# rng_1_0.net
KiCad netlist of a schematic drawn in EAGLE
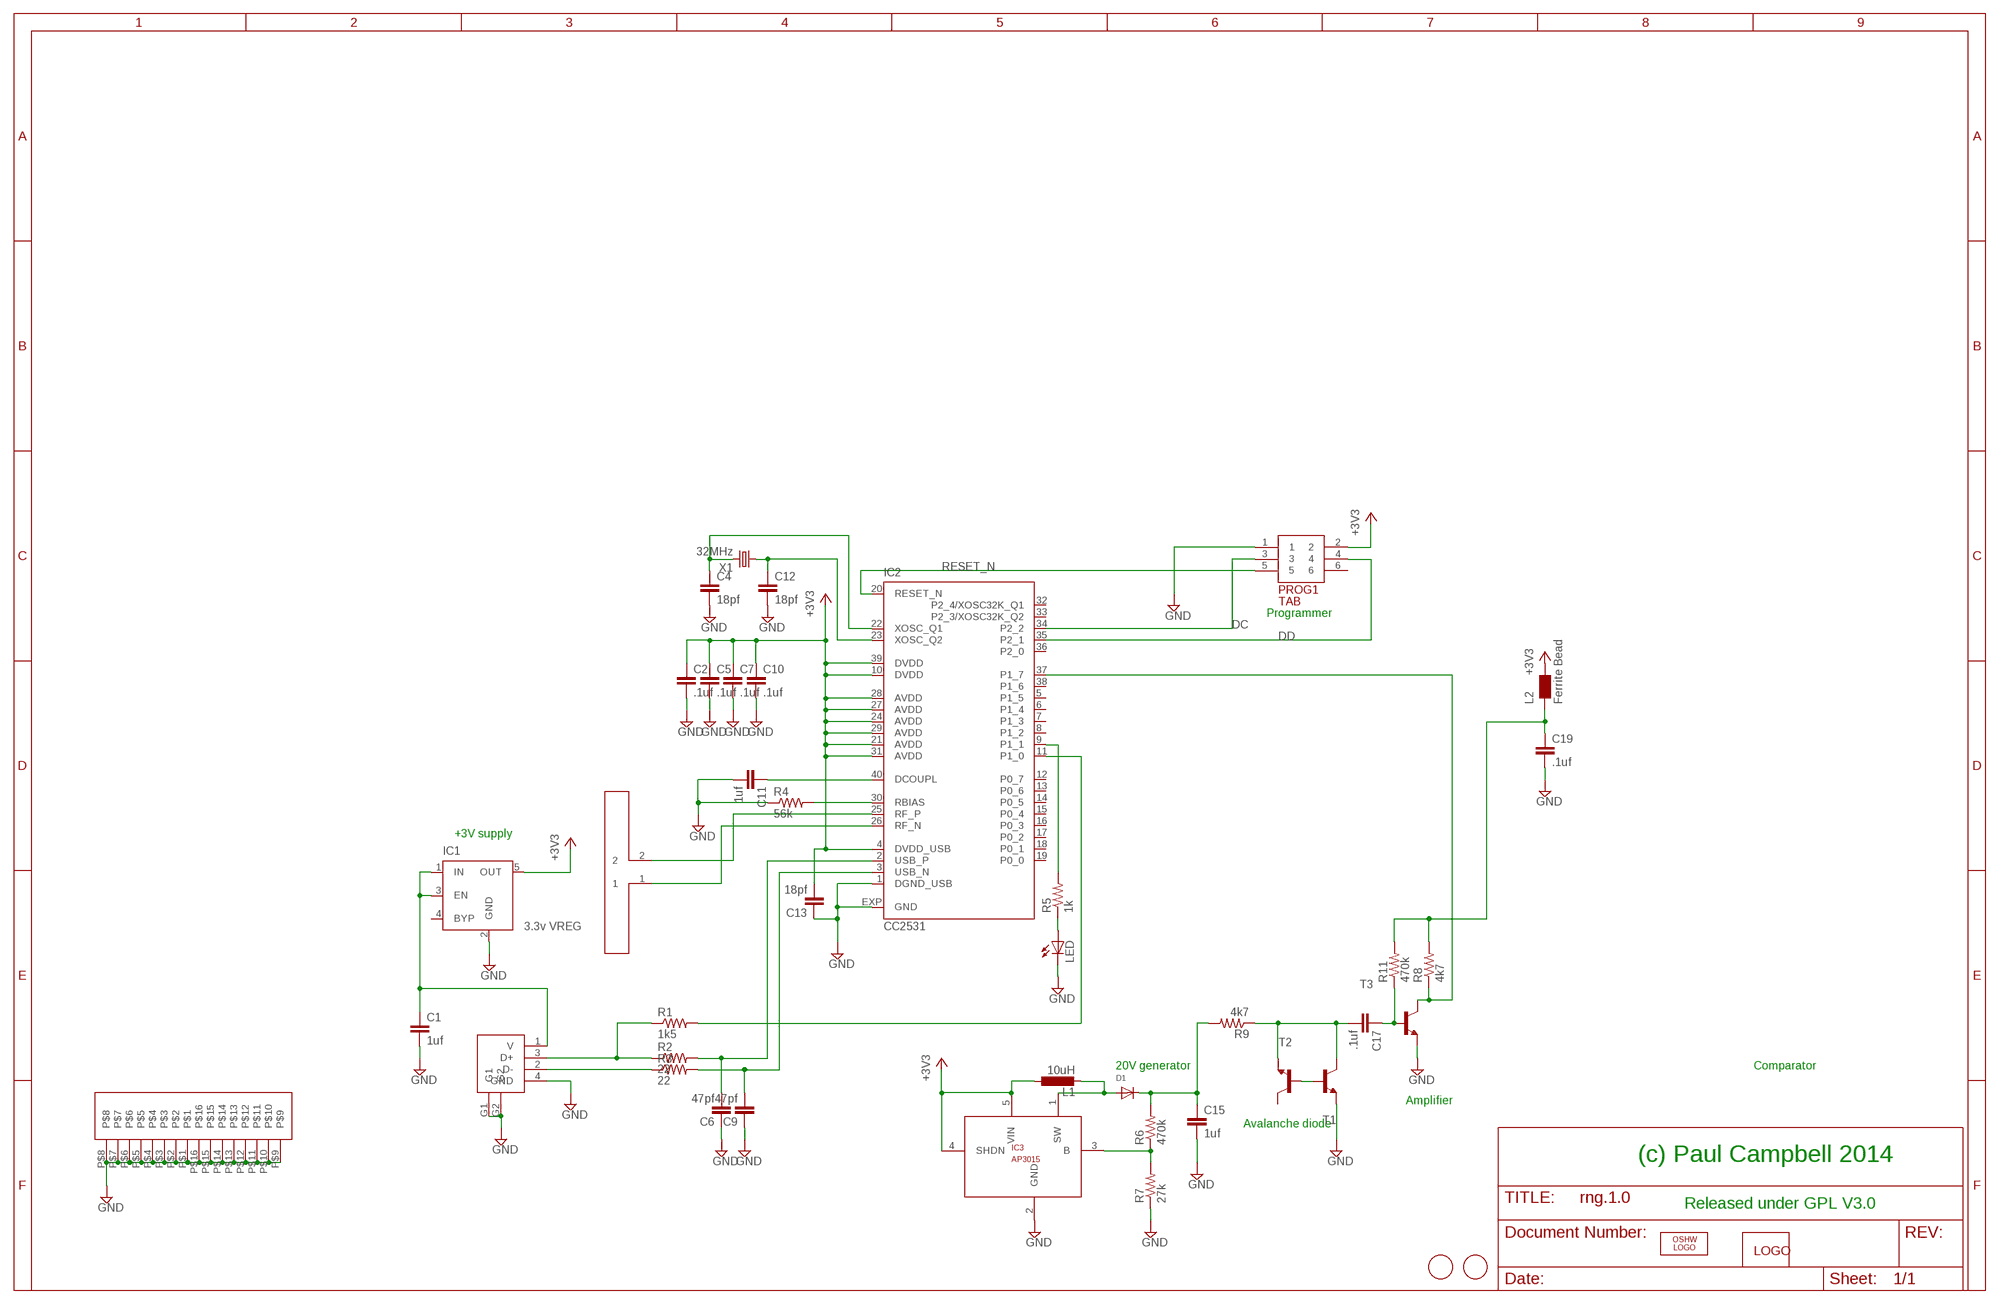
[diagram p0: schematic, sheet 1]

(export (version "E")
  (design (tool "Eeschema 10.0.6"))
  (components
    (comp (ref "C1")
      (value "1uf")
      (footprint "eagle-import:C0603")
      (libsource (lib "eagle-import") (part "C-EUC0603"))
    )
    (comp (ref "C2")
      (value ".1uf")
      (footprint "eagle-import:C0603")
      (libsource (lib "eagle-import") (part "C-EUC0603"))
    )
    (comp (ref "C4")
      (value "18pf")
      (footprint "eagle-import:C0603")
      (libsource (lib "eagle-import") (part "C-EUC0603"))
    )
    (comp (ref "C5")
      (value ".1uf")
      (footprint "eagle-import:C0603K")
      (libsource (lib "eagle-import") (part "C-EUC0603K"))
    )
    (comp (ref "C6")
      (value "47pf")
      (footprint "eagle-import:C0603")
      (libsource (lib "eagle-import") (part "C-EUC0603"))
    )
    (comp (ref "C7")
      (value ".1uf")
      (footprint "eagle-import:C0603")
      (libsource (lib "eagle-import") (part "C-EUC0603"))
    )
    (comp (ref "C9")
      (value "47pf")
      (footprint "eagle-import:C0603")
      (libsource (lib "eagle-import") (part "C-EUC0603"))
    )
    (comp (ref "C10")
      (value ".1uf")
      (footprint "eagle-import:C0603")
      (libsource (lib "eagle-import") (part "C-EUC0603"))
    )
    (comp (ref "C11")
      (value "1uf")
      (footprint "eagle-import:C0603")
      (libsource (lib "eagle-import") (part "C-EUC0603"))
    )
    (comp (ref "C12")
      (value "18pf")
      (footprint "eagle-import:C0603")
      (libsource (lib "eagle-import") (part "C-EUC0603"))
    )
    (comp (ref "C13")
      (value "18pf")
      (footprint "eagle-import:C0603")
      (libsource (lib "eagle-import") (part "C-EUC0603"))
    )
    (comp (ref "C15")
      (value "1uf")
      (footprint "eagle-import:C0603")
      (libsource (lib "eagle-import") (part "C-EUC0603"))
    )
    (comp (ref "C17")
      (value ".1uf")
      (footprint "eagle-import:C0603")
      (libsource (lib "eagle-import") (part "C-EUC0603"))
    )
    (comp (ref "C19")
      (value ".1uf")
      (footprint "eagle-import:C0603")
      (libsource (lib "eagle-import") (part "C-EUC0603"))
    )
    (comp (ref "D1")
      (value "DIODESOD-323F")
      (footprint "eagle-import:SOD-323F")
      (libsource (lib "eagle-import") (part "DIODESOD-323F"))
    )
    (comp (ref "IC1")
      (value "3.3v VREG")
      (footprint "eagle-import:SOT23-5")
      (libsource (lib "eagle-import") (part "MIC5219XX"))
    )
    (comp (ref "IC2")
      (value "CC2531")
      (footprint "eagle-import:RHA_S-PVQFN-N40")
      (fields (field (name "MPN") "CC2531F256RHAT"))
      (libsource (lib "eagle-import") (part "CC2531"))
    )
    (comp (ref "IC3")
      (value "AP3015")
      (footprint "eagle-import:SOT23-5")
      (libsource (lib "eagle-import") (part "AP3015"))
    )
    (comp (ref "L1")
      (value "10uH")
      (footprint "eagle-import:L2012C")
      (libsource (lib "eagle-import") (part "L-EUL2012C"))
    )
    (comp (ref "L2")
      (value "Ferrite Bead")
      (footprint "eagle-import:0805")
      (libsource (lib "eagle-import") (part "WE-CBF_0805"))
    )
    (comp (ref "LED")
      (value "LEDCHIP-LED0603")
      (footprint "eagle-import:CHIP-LED0603")
      (libsource (lib "eagle-import") (part "LEDCHIP-LED0603"))
    )
    (comp (ref "LOGO1")
      (value "OSHW_LOGO_FILLX0100-NT")
      (footprint "eagle-import:OSHW_FILLX100_NOTEXT")
      (libsource (lib "eagle-import") (part "OSHW_LOGO_FILLX0100-NT"))
    )
    (comp (ref "PROG1")
      (value "TAB")
      (footprint "eagle-import:TAG")
      (libsource (lib "eagle-import") (part "TAB"))
    )
    (comp (ref "R1")
      (value "1k5")
      (footprint "eagle-import:R0603")
      (libsource (lib "eagle-import") (part "R-US_R0603"))
    )
    (comp (ref "R2")
      (value "22")
      (footprint "eagle-import:R0603")
      (libsource (lib "eagle-import") (part "R-US_R0603"))
    )
    (comp (ref "R3")
      (value "22")
      (footprint "eagle-import:R0603")
      (libsource (lib "eagle-import") (part "R-US_R0603"))
    )
    (comp (ref "R4")
      (value "56k")
      (footprint "eagle-import:R0603")
      (libsource (lib "eagle-import") (part "R-US_R0603"))
    )
    (comp (ref "R5")
      (value "1k")
      (footprint "eagle-import:R0603")
      (libsource (lib "eagle-import") (part "R-US_R0603"))
    )
    (comp (ref "R6")
      (value "470k")
      (footprint "eagle-import:R0603")
      (libsource (lib "eagle-import") (part "R-US_R0603"))
    )
    (comp (ref "R7")
      (value "27k")
      (footprint "eagle-import:R0603")
      (libsource (lib "eagle-import") (part "R-US_R0603"))
    )
    (comp (ref "R8")
      (value "4k7")
      (footprint "eagle-import:R0603")
      (libsource (lib "eagle-import") (part "R-US_R0603"))
    )
    (comp (ref "R9")
      (value "4k7")
      (footprint "eagle-import:R0603")
      (libsource (lib "eagle-import") (part "R-US_R0603"))
    )
    (comp (ref "R11")
      (value "470k")
      (footprint "eagle-import:R0603")
      (libsource (lib "eagle-import") (part "R-US_R0603"))
    )
    (comp (ref "T1")
      (value "BCF32-NPN-SOT23-BEC")
      (footprint "eagle-import:SOT23-BEC")
      (libsource (lib "eagle-import") (part "-NPN-SOT23-BECBCF32"))
    )
    (comp (ref "T2")
      (value "BCF32-NPN-SOT23-BEC")
      (footprint "eagle-import:SOT23-BEC")
      (libsource (lib "eagle-import") (part "-NPN-SOT23-BECBCF32"))
    )
    (comp (ref "T3")
      (value "BCF32-NPN-SOT23-BEC")
      (footprint "eagle-import:SOT23-BEC")
      (libsource (lib "eagle-import") (part "-NPN-SOT23-BECBCF32"))
    )
    (comp (ref "U$1")
      (value "USB-RAW")
      (footprint "eagle-import:USBY")
      (libsource (lib "eagle-import") (part "USB-RAW"))
    )
    (comp (ref "U$2")
      (value "DIPOLEDIPOLE1")
      (footprint "eagle-import:DIPOLE")
      (libsource (lib "eagle-import") (part "DIPOLEDIPOLE1"))
    )
    (comp (ref "U$3")
      (value "FIDUCIAL")
      (footprint "eagle-import:FIDUCIAL_1MM")
      (libsource (lib "eagle-import") (part "FIDUCIAL"))
    )
    (comp (ref "U$4")
      (value "FIDUCIAL")
      (footprint "eagle-import:FIDUCIAL_1MM")
      (libsource (lib "eagle-import") (part "FIDUCIAL"))
    )
    (comp (ref "U$5")
      (value "MOONBASE-LOGO")
      (footprint "eagle-import:MOONBASE-LOGO")
      (libsource (lib "eagle-import") (part "MOONBASE-LOGO"))
    )
    (comp (ref "U$6")
      (value "BMI-S-2-09")
      (footprint "eagle-import:SHIELD-209")
      (libsource (lib "eagle-import") (part "BMI-S-2-09"))
    )
    (comp (ref "X1")
      (value "32MHz")
      (footprint "eagle-import:SM49")
      (libsource (lib "eagle-import") (part "CRYSTALSM49"))
    )
  )
  (nets
    (net (code "1") (name "+3V3") (class "Default")
      (node (ref "C10") (pin "1") (pinfunction "1_1") (pintype "passive"))
      (node (ref "C13") (pin "2") (pinfunction "2_2") (pintype "passive"))
      (node (ref "C2") (pin "1") (pinfunction "1_1") (pintype "passive"))
      (node (ref "C5") (pin "1") (pinfunction "1_1") (pintype "passive"))
      (node (ref "C7") (pin "1") (pinfunction "1_1") (pintype "passive"))
      (node (ref "IC1") (pin "5") (pinfunction "OUT_5") (pintype "output"))
      (node (ref "IC2") (pin "10") (pinfunction "DVDD_10") (pintype "power_in"))
      (node (ref "IC2") (pin "21") (pinfunction "AVDD_21") (pintype "power_in"))
      (node (ref "IC2") (pin "24") (pinfunction "AVDD_24") (pintype "power_in"))
      (node (ref "IC2") (pin "27") (pinfunction "AVDD_27") (pintype "power_in"))
      (node (ref "IC2") (pin "28") (pinfunction "AVDD_28") (pintype "power_in"))
      (node (ref "IC2") (pin "29") (pinfunction "AVDD_29") (pintype "power_in"))
      (node (ref "IC2") (pin "31") (pinfunction "AVDD_31") (pintype "power_in"))
      (node (ref "IC2") (pin "39") (pinfunction "DVDD_39") (pintype "power_in"))
      (node (ref "IC2") (pin "4") (pinfunction "DVDD_USB_4") (pintype "power_in"))
      (node (ref "IC3") (pin "4") (pinfunction "SHDN_4") (pintype "bidirectional"))
      (node (ref "IC3") (pin "5") (pinfunction "VIN_5") (pintype "bidirectional"))
      (node (ref "L1") (pin "1") (pinfunction "1_1") (pintype "passive"))
      (node (ref "L2") (pin "2") (pinfunction "2_2") (pintype "passive"))
      (node (ref "PROG1") (pin "2") (pinfunction "2_2") (pintype "bidirectional"))
    )
    (net (code "2") (name "/DC") (class "Default")
      (node (ref "IC2") (pin "34") (pinfunction "P2_2_34") (pintype "bidirectional"))
      (node (ref "PROG1") (pin "3") (pinfunction "3_3") (pintype "bidirectional"))
    )
    (net (code "3") (name "/DD") (class "Default")
      (node (ref "IC2") (pin "35") (pinfunction "P2_1_35") (pintype "bidirectional"))
      (node (ref "PROG1") (pin "4") (pinfunction "4_4") (pintype "bidirectional"))
    )
    (net (code "4") (name "/RESET_N") (class "Default")
      (node (ref "IC2") (pin "20") (pinfunction "RESET_N_20") (pintype "input"))
      (node (ref "PROG1") (pin "5") (pinfunction "5_5") (pintype "bidirectional"))
    )
    (net (code "5") (name "GND") (class "Default")
      (node (ref "C1") (pin "2") (pinfunction "2_2") (pintype "passive"))
      (node (ref "C10") (pin "2") (pinfunction "2_2") (pintype "passive"))
      (node (ref "C11") (pin "2") (pinfunction "2_2") (pintype "passive"))
      (node (ref "C12") (pin "2") (pinfunction "2_2") (pintype "passive"))
      (node (ref "C13") (pin "1") (pinfunction "1_1") (pintype "passive"))
      (node (ref "C15") (pin "2") (pinfunction "2_2") (pintype "passive"))
      (node (ref "C19") (pin "2") (pinfunction "2_2") (pintype "passive"))
      (node (ref "C2") (pin "2") (pinfunction "2_2") (pintype "passive"))
      (node (ref "C4") (pin "2") (pinfunction "2_2") (pintype "passive"))
      (node (ref "C5") (pin "2") (pinfunction "2_2") (pintype "passive"))
      (node (ref "C6") (pin "1") (pinfunction "1_1") (pintype "passive"))
      (node (ref "C7") (pin "2") (pinfunction "2_2") (pintype "passive"))
      (node (ref "C9") (pin "1") (pinfunction "1_1") (pintype "passive"))
      (node (ref "IC1") (pin "2") (pinfunction "GND_2") (pintype "power_in"))
      (node (ref "IC2") (pin "1") (pinfunction "DGND_USB_1") (pintype "power_in"))
      (node (ref "IC2") (pin "EXP") (pinfunction "GND_EXP") (pintype "passive"))
      (node (ref "IC3") (pin "2") (pinfunction "GND_2") (pintype "bidirectional"))
      (node (ref "LED") (pin "C") (pinfunction "C_C") (pintype "passive"))
      (node (ref "PROG1") (pin "1") (pinfunction "1_1") (pintype "bidirectional"))
      (node (ref "R4") (pin "1") (pinfunction "1_1") (pintype "passive"))
      (node (ref "R7") (pin "1") (pinfunction "1_1") (pintype "passive"))
      (node (ref "T2") (pin "E") (pinfunction "E_E") (pintype "passive"))
      (node (ref "T3") (pin "E") (pinfunction "E_E") (pintype "passive"))
      (node (ref "U$1") (pin "4") (pinfunction "GND_4") (pintype "bidirectional"))
      (node (ref "U$1") (pin "G1") (pinfunction "G1_G1") (pintype "bidirectional"))
      (node (ref "U$1") (pin "G2") (pinfunction "G2_G2") (pintype "bidirectional"))
      (node (ref "U$6") (pin "P$1") (pinfunction "P$1_P$1") (pintype "bidirectional"))
      (node (ref "U$6") (pin "P$10") (pinfunction "P$10_P$10") (pintype "bidirectional"))
      (node (ref "U$6") (pin "P$11") (pinfunction "P$11_P$11") (pintype "bidirectional"))
      (node (ref "U$6") (pin "P$12") (pinfunction "P$12_P$12") (pintype "bidirectional"))
      (node (ref "U$6") (pin "P$13") (pinfunction "P$13_P$13") (pintype "bidirectional"))
      (node (ref "U$6") (pin "P$14") (pinfunction "P$14_P$14") (pintype "bidirectional"))
      (node (ref "U$6") (pin "P$15") (pinfunction "P$15_P$15") (pintype "bidirectional"))
      (node (ref "U$6") (pin "P$16") (pinfunction "P$16_P$16") (pintype "bidirectional"))
      (node (ref "U$6") (pin "P$2") (pinfunction "P$2_P$2") (pintype "bidirectional"))
      (node (ref "U$6") (pin "P$3") (pinfunction "P$3_P$3") (pintype "bidirectional"))
      (node (ref "U$6") (pin "P$4") (pinfunction "P$4_P$4") (pintype "bidirectional"))
      (node (ref "U$6") (pin "P$5") (pinfunction "P$5_P$5") (pintype "bidirectional"))
      (node (ref "U$6") (pin "P$6") (pinfunction "P$6_P$6") (pintype "bidirectional"))
      (node (ref "U$6") (pin "P$7") (pinfunction "P$7_P$7") (pintype "bidirectional"))
      (node (ref "U$6") (pin "P$8") (pinfunction "P$8_P$8") (pintype "bidirectional"))
      (node (ref "U$6") (pin "P$9") (pinfunction "P$9_P$9") (pintype "bidirectional"))
    )
    (net (code "6") (name "Net-(C15-Pad1)") (class "Default")
      (node (ref "C15") (pin "1") (pinfunction "1_1") (pintype "passive"))
      (node (ref "D1") (pin "C") (pinfunction "C_C") (pintype "passive"))
      (node (ref "R6") (pin "2") (pinfunction "2_2") (pintype "passive"))
      (node (ref "R9") (pin "2") (pinfunction "2_2") (pintype "passive"))
    )
    (net (code "7") (name "Net-(C17-Pad1)") (class "Default")
      (node (ref "C17") (pin "1") (pinfunction "1_1") (pintype "passive"))
      (node (ref "R11") (pin "1") (pinfunction "1_1") (pintype "passive"))
      (node (ref "T3") (pin "B") (pinfunction "B_B") (pintype "passive"))
    )
    (net (code "8") (name "Net-(C17-Pad2)") (class "Default")
      (node (ref "C17") (pin "2") (pinfunction "2_2") (pintype "passive"))
      (node (ref "R9") (pin "1") (pinfunction "1_1") (pintype "passive"))
      (node (ref "T1") (pin "E") (pinfunction "E_E") (pintype "passive"))
      (node (ref "T2") (pin "C") (pinfunction "C_C") (pintype "passive"))
    )
    (net (code "9") (name "Net-(C19-Pad1)") (class "Default")
      (node (ref "C19") (pin "1") (pinfunction "1_1") (pintype "passive"))
      (node (ref "L2") (pin "1") (pinfunction "1_1") (pintype "passive"))
      (node (ref "R11") (pin "2") (pinfunction "2_2") (pintype "passive"))
      (node (ref "R8") (pin "2") (pinfunction "2_2") (pintype "passive"))
    )
    (net (code "10") (name "Net-(IC1-EN)") (class "Default")
      (node (ref "C1") (pin "1") (pinfunction "1_1") (pintype "passive"))
      (node (ref "IC1") (pin "1") (pinfunction "IN_1") (pintype "input"))
      (node (ref "IC1") (pin "3") (pinfunction "EN_3") (pintype "input"))
      (node (ref "U$1") (pin "1") (pinfunction "V_1") (pintype "bidirectional"))
    )
    (net (code "11") (name "Net-(IC2-DCOUPL)") (class "Default")
      (node (ref "C11") (pin "1") (pinfunction "1_1") (pintype "passive"))
      (node (ref "IC2") (pin "40") (pinfunction "DCOUPL_40") (pintype "power_in"))
    )
    (net (code "12") (name "Net-(IC2-P1_0)") (class "Default")
      (node (ref "IC2") (pin "11") (pinfunction "P1_0_11") (pintype "bidirectional"))
      (node (ref "R1") (pin "2") (pinfunction "2_2") (pintype "passive"))
    )
    (net (code "13") (name "Net-(IC2-P1_1)") (class "Default")
      (node (ref "IC2") (pin "9") (pinfunction "P1_1_9") (pintype "bidirectional"))
      (node (ref "R5") (pin "2") (pinfunction "2_2") (pintype "passive"))
    )
    (net (code "14") (name "Net-(IC2-P1_7)") (class "Default")
      (node (ref "IC2") (pin "37") (pinfunction "P1_7_37") (pintype "bidirectional"))
      (node (ref "R8") (pin "1") (pinfunction "1_1") (pintype "passive"))
      (node (ref "T3") (pin "C") (pinfunction "C_C") (pintype "passive"))
    )
    (net (code "15") (name "Net-(IC2-RBIAS)") (class "Default")
      (node (ref "IC2") (pin "30") (pinfunction "RBIAS_30") (pintype "bidirectional"))
      (node (ref "R4") (pin "2") (pinfunction "2_2") (pintype "passive"))
    )
    (net (code "16") (name "Net-(IC2-RF_N)") (class "Default")
      (node (ref "IC2") (pin "26") (pinfunction "RF_N_26") (pintype "bidirectional"))
      (node (ref "U$2") (pin "1") (pinfunction "1_1") (pintype "bidirectional"))
    )
    (net (code "17") (name "Net-(IC2-RF_P)") (class "Default")
      (node (ref "IC2") (pin "25") (pinfunction "RF_P_25") (pintype "bidirectional"))
      (node (ref "U$2") (pin "2") (pinfunction "2_2") (pintype "bidirectional"))
    )
    (net (code "18") (name "Net-(IC2-USB_N)") (class "Default")
      (node (ref "C9") (pin "2") (pinfunction "2_2") (pintype "passive"))
      (node (ref "IC2") (pin "3") (pinfunction "USB_N_3") (pintype "bidirectional"))
      (node (ref "R3") (pin "2") (pinfunction "2_2") (pintype "passive"))
    )
    (net (code "19") (name "Net-(IC2-USB_P)") (class "Default")
      (node (ref "C6") (pin "2") (pinfunction "2_2") (pintype "passive"))
      (node (ref "IC2") (pin "2") (pinfunction "USB_P_2") (pintype "bidirectional"))
      (node (ref "R2") (pin "2") (pinfunction "2_2") (pintype "passive"))
    )
    (net (code "20") (name "Net-(IC2-XOSC_Q1)") (class "Default")
      (node (ref "C4") (pin "1") (pinfunction "1_1") (pintype "passive"))
      (node (ref "IC2") (pin "22") (pinfunction "XOSC_Q1_22") (pintype "bidirectional"))
      (node (ref "X1") (pin "2") (pinfunction "2_2") (pintype "passive"))
    )
    (net (code "21") (name "Net-(IC2-XOSC_Q2)") (class "Default")
      (node (ref "C12") (pin "1") (pinfunction "1_1") (pintype "passive"))
      (node (ref "IC2") (pin "23") (pinfunction "XOSC_Q2_23") (pintype "bidirectional"))
      (node (ref "X1") (pin "1") (pinfunction "1_1") (pintype "passive"))
    )
    (net (code "22") (name "Net-(IC3-B)") (class "Default")
      (node (ref "IC3") (pin "3") (pinfunction "B_3") (pintype "bidirectional"))
      (node (ref "R6") (pin "1") (pinfunction "1_1") (pintype "passive"))
      (node (ref "R7") (pin "2") (pinfunction "2_2") (pintype "passive"))
    )
    (net (code "23") (name "Net-(IC3-SW)") (class "Default")
      (node (ref "D1") (pin "A") (pinfunction "A_A") (pintype "passive"))
      (node (ref "IC3") (pin "1") (pinfunction "SW_1") (pintype "bidirectional"))
      (node (ref "L1") (pin "2") (pinfunction "2_2") (pintype "passive"))
    )
    (net (code "24") (name "Net-(LED-PadA)") (class "Default")
      (node (ref "LED") (pin "A") (pinfunction "A_A") (pintype "passive"))
      (node (ref "R5") (pin "1") (pinfunction "1_1") (pintype "passive"))
    )
    (net (code "25") (name "Net-(T1-PadB)") (class "Default")
      (node (ref "T1") (pin "B") (pinfunction "B_B") (pintype "passive"))
      (node (ref "T2") (pin "B") (pinfunction "B_B") (pintype "passive"))
    )
    (net (code "26") (name "Net-(U$1-D+)") (class "Default")
      (node (ref "R1") (pin "1") (pinfunction "1_1") (pintype "passive"))
      (node (ref "R2") (pin "1") (pinfunction "1_1") (pintype "passive"))
      (node (ref "U$1") (pin "3") (pinfunction "D+_3") (pintype "bidirectional"))
    )
    (net (code "27") (name "Net-(U$1-D-)") (class "Default")
      (node (ref "R3") (pin "1") (pinfunction "1_1") (pintype "passive"))
      (node (ref "U$1") (pin "2") (pinfunction "D-_2") (pintype "bidirectional"))
    )
    (net (code "28") (name "unconnected-(IC1-BYP-Pad4)") (class "Default")
      (node (ref "IC1") (pin "4") (pinfunction "BYP_4") (pintype "passive"))
    )
    (net (code "29") (name "unconnected-(IC2-P0_0-Pad19)") (class "Default")
      (node (ref "IC2") (pin "19") (pinfunction "P0_0_19") (pintype "bidirectional"))
    )
    (net (code "30") (name "unconnected-(IC2-P0_1-Pad18)") (class "Default")
      (node (ref "IC2") (pin "18") (pinfunction "P0_1_18") (pintype "bidirectional"))
    )
    (net (code "31") (name "unconnected-(IC2-P0_2-Pad17)") (class "Default")
      (node (ref "IC2") (pin "17") (pinfunction "P0_2_17") (pintype "bidirectional"))
    )
    (net (code "32") (name "unconnected-(IC2-P0_3-Pad16)") (class "Default")
      (node (ref "IC2") (pin "16") (pinfunction "P0_3_16") (pintype "bidirectional"))
    )
    (net (code "33") (name "unconnected-(IC2-P0_4-Pad15)") (class "Default")
      (node (ref "IC2") (pin "15") (pinfunction "P0_4_15") (pintype "bidirectional"))
    )
    (net (code "34") (name "unconnected-(IC2-P0_5-Pad14)") (class "Default")
      (node (ref "IC2") (pin "14") (pinfunction "P0_5_14") (pintype "bidirectional"))
    )
    (net (code "35") (name "unconnected-(IC2-P0_6-Pad13)") (class "Default")
      (node (ref "IC2") (pin "13") (pinfunction "P0_6_13") (pintype "bidirectional"))
    )
    (net (code "36") (name "unconnected-(IC2-P0_7-Pad12)") (class "Default")
      (node (ref "IC2") (pin "12") (pinfunction "P0_7_12") (pintype "bidirectional"))
    )
    (net (code "37") (name "unconnected-(IC2-P1_2-Pad8)") (class "Default")
      (node (ref "IC2") (pin "8") (pinfunction "P1_2_8") (pintype "bidirectional"))
    )
    (net (code "38") (name "unconnected-(IC2-P1_3-Pad7)") (class "Default")
      (node (ref "IC2") (pin "7") (pinfunction "P1_3_7") (pintype "bidirectional"))
    )
    (net (code "39") (name "unconnected-(IC2-P1_4-Pad6)") (class "Default")
      (node (ref "IC2") (pin "6") (pinfunction "P1_4_6") (pintype "bidirectional"))
    )
    (net (code "40") (name "unconnected-(IC2-P1_5-Pad5)") (class "Default")
      (node (ref "IC2") (pin "5") (pinfunction "P1_5_5") (pintype "bidirectional"))
    )
    (net (code "41") (name "unconnected-(IC2-P1_6-Pad38)") (class "Default")
      (node (ref "IC2") (pin "38") (pinfunction "P1_6_38") (pintype "bidirectional"))
    )
    (net (code "42") (name "unconnected-(IC2-P2_0-Pad36)") (class "Default")
      (node (ref "IC2") (pin "36") (pinfunction "P2_0_36") (pintype "bidirectional"))
    )
    (net (code "43") (name "unconnected-(IC2-P2_3{slash}XOSC32K_Q2-Pad33)") (class "Default")
      (node (ref "IC2") (pin "33") (pinfunction "P2_3/XOSC32K_Q2_33") (pintype "bidirectional"))
    )
    (net (code "44") (name "unconnected-(IC2-P2_4{slash}XOSC32K_Q1-Pad32)") (class "Default")
      (node (ref "IC2") (pin "32") (pinfunction "P2_4/XOSC32K_Q1_32") (pintype "bidirectional"))
    )
    (net (code "45") (name "unconnected-(PROG1-Pad6)") (class "Default")
      (node (ref "PROG1") (pin "6") (pinfunction "6_6") (pintype "bidirectional"))
    )
    (net (code "46") (name "unconnected-(T1-PadC)") (class "Default")
      (node (ref "T1") (pin "C") (pinfunction "C_C") (pintype "passive"))
    )
  )
)
